# 2019_Dashboard_2_4_19.net
KiCad netlist of a schematic drawn in EAGLE
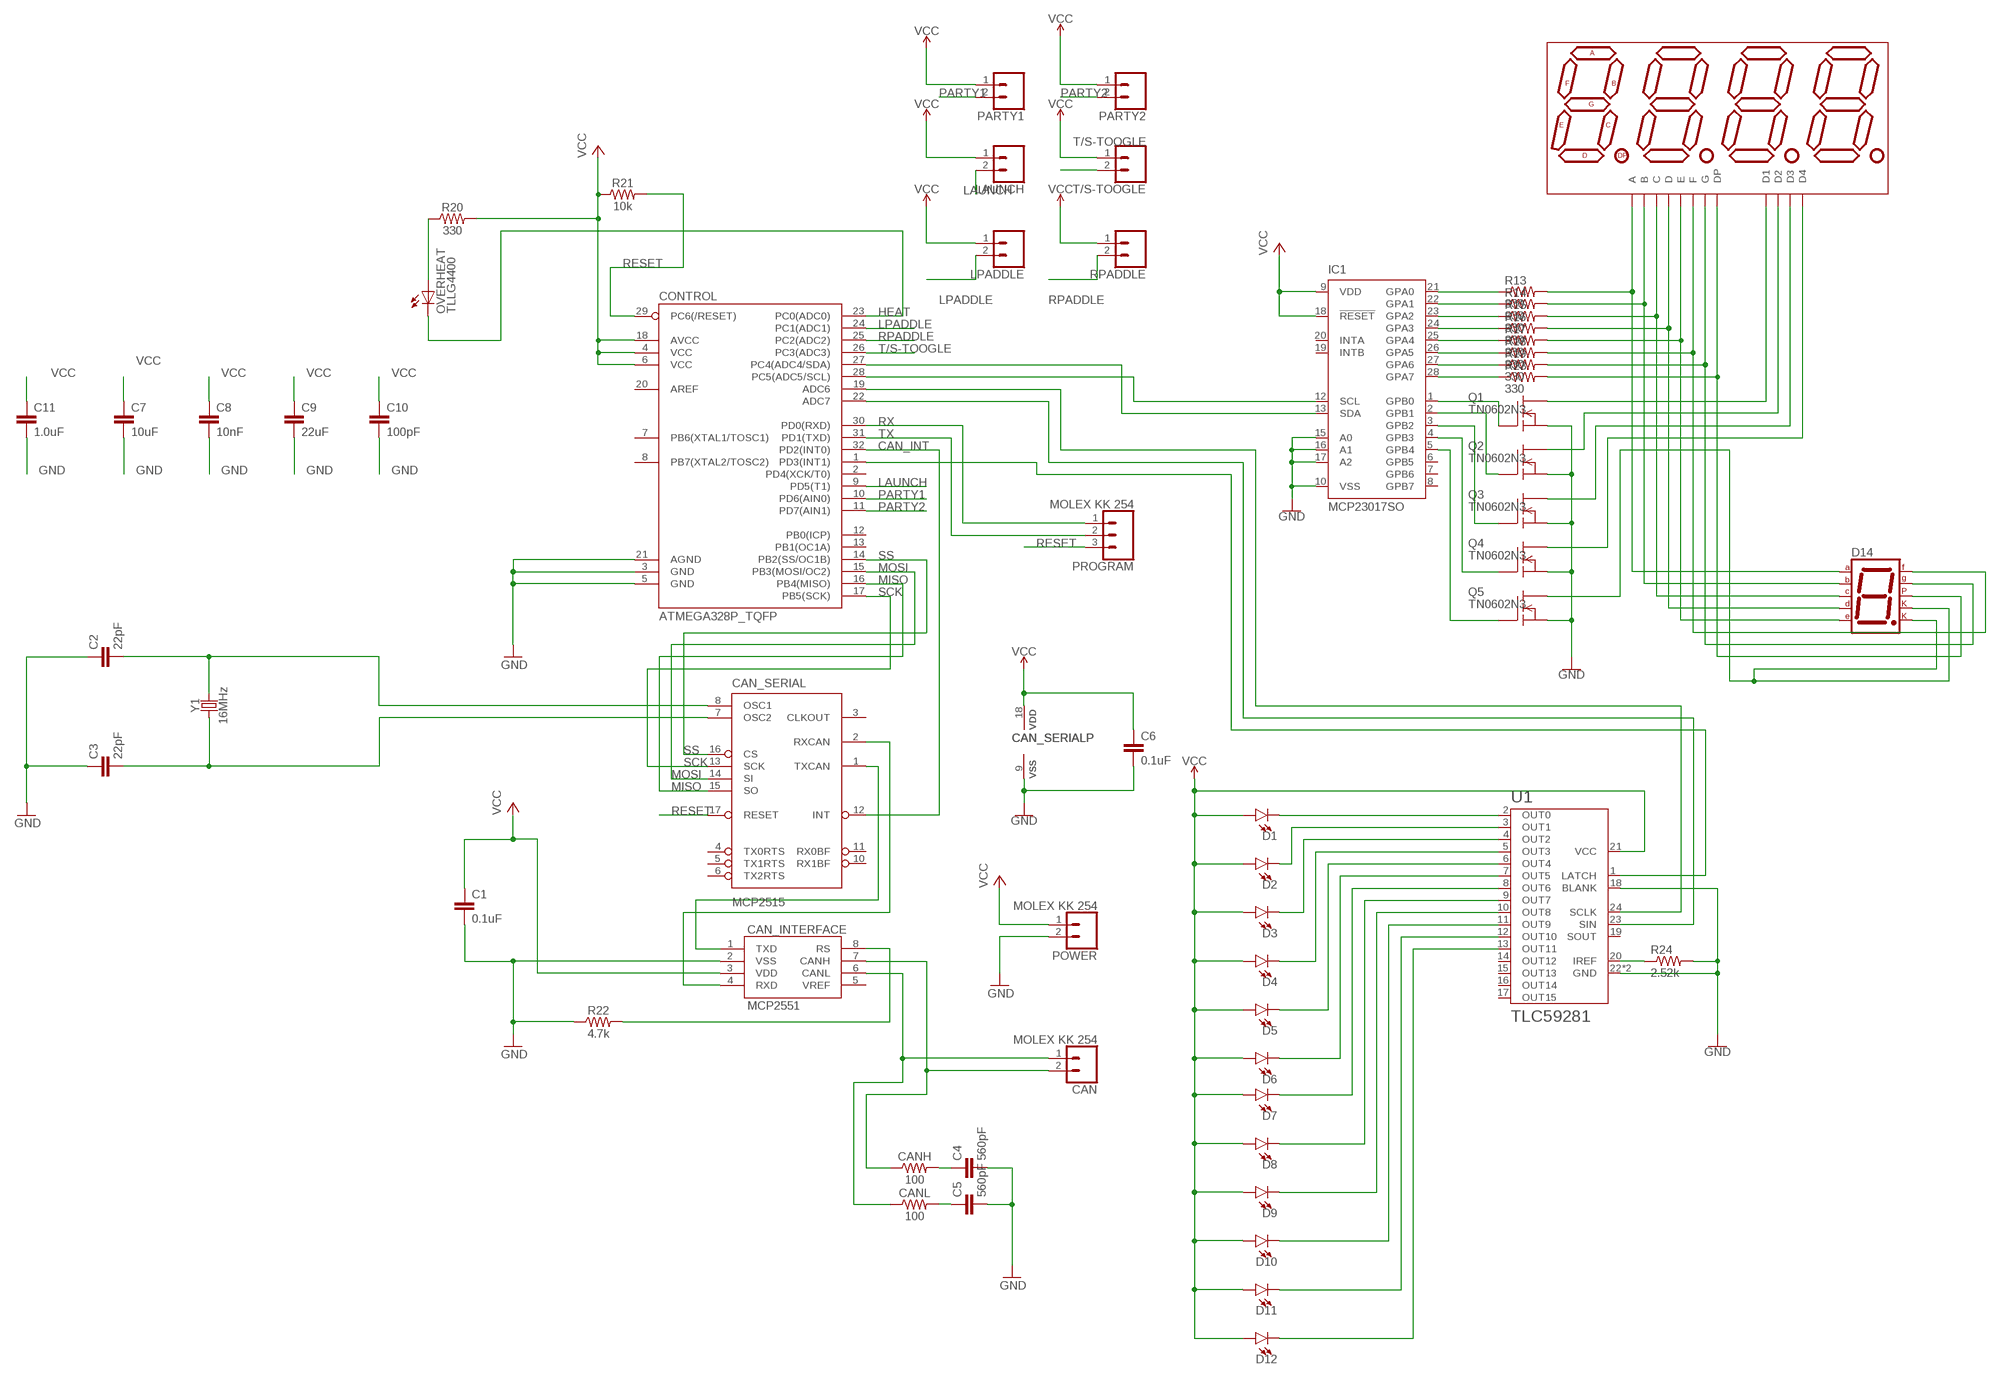
[diagram p0: schematic, sheet 1]

(export (version "E")
  (design (tool "Eeschema 10.0.6"))
  (components
    (comp (ref "C1")
      (value "0.1uF")
      (footprint "eagle-import:0603")
      (libsource (lib "eagle-import") (part "0.1UF-0603-25V-(+80/-20%)"))
    )
    (comp (ref "C2")
      (value "22pF")
      (footprint "eagle-import:0603")
      (libsource (lib "eagle-import") (part "22PF-0603-50V-5%"))
    )
    (comp (ref "C3")
      (value "22pF")
      (footprint "eagle-import:0603")
      (libsource (lib "eagle-import") (part "22PF-0603-50V-5%"))
    )
    (comp (ref "C4")
      (value "560pF")
      (footprint "eagle-import:0603")
      (libsource (lib "eagle-import") (part "560PF-0603-50V-5%"))
    )
    (comp (ref "C5")
      (value "560pF")
      (footprint "eagle-import:0603")
      (libsource (lib "eagle-import") (part "560PF-0603-50V-5%"))
    )
    (comp (ref "C6")
      (value "0.1uF")
      (footprint "eagle-import:0402")
      (libsource (lib "eagle-import") (part "0.1UF-0402-16V-10%"))
    )
    (comp (ref "C7")
      (value "10uF")
      (footprint "eagle-import:0805")
      (libsource (lib "eagle-import") (part "10UF-0805-10V-10%"))
    )
    (comp (ref "C8")
      (value "10nF")
      (footprint "eagle-import:0603")
      (libsource (lib "eagle-import") (part "10NF-0603-50V-10%"))
    )
    (comp (ref "C9")
      (value "22uF")
      (footprint "eagle-import:0805")
      (libsource (lib "eagle-import") (part "22UF-0805-6.3V-20%"))
    )
    (comp (ref "C10")
      (value "100pF")
      (footprint "eagle-import:0603")
      (libsource (lib "eagle-import") (part "100PF-0603-50V-5%"))
    )
    (comp (ref "C11")
      (value "1.0uF")
      (footprint "eagle-import:0805")
      (libsource (lib "eagle-import") (part "1.0UF-0805-25V-(+80/-20%)"))
    )
    (comp (ref "CAN")
      (value "MOLEX KK 254")
      (footprint "eagle-import:1X02")
      (libsource (lib "eagle-import") (part "CONN_02"))
    )
    (comp (ref "CANH")
      (value "100")
      (footprint "eagle-import:0603")
      (libsource (lib "eagle-import") (part "100OHM-0603-1/4W-5%"))
    )
    (comp (ref "CANL")
      (value "100")
      (footprint "eagle-import:0603")
      (libsource (lib "eagle-import") (part "100OHM-0603-1/4W-5%"))
    )
    (comp (ref "CAN_INTERFACE")
      (value "MCP2551")
      (footprint "eagle-import:SO08")
      (libsource (lib "eagle-import") (part "MCP2551"))
    )
    (comp (ref "CAN_SERIAL")
      (value "MCP2515")
      (footprint "eagle-import:SO18W")
      (libsource (lib "eagle-import") (part "MCP2515(MCP2510)SO"))
    )
    (comp (ref "CONTROL")
      (value "ATMEGA328P_TQFP")
      (footprint "eagle-import:TQFP32-08")
      (libsource (lib "eagle-import") (part "ATMEGA328P_TQFP"))
    )
    (comp (ref "D1")
      (value "LED5MM")
      (footprint "eagle-import:LED_5MM")
      (libsource (lib "eagle-import") (part "LED5MM"))
    )
    (comp (ref "D2")
      (value "LED5MM")
      (footprint "eagle-import:LED_5MM")
      (libsource (lib "eagle-import") (part "LED5MM"))
    )
    (comp (ref "D3")
      (value "LED5MM")
      (footprint "eagle-import:LED_5MM")
      (libsource (lib "eagle-import") (part "LED5MM"))
    )
    (comp (ref "D4")
      (value "LED5MM")
      (footprint "eagle-import:LED_5MM")
      (libsource (lib "eagle-import") (part "LED5MM"))
    )
    (comp (ref "D5")
      (value "LED5MM")
      (footprint "eagle-import:LED_5MM")
      (libsource (lib "eagle-import") (part "LED5MM"))
    )
    (comp (ref "D6")
      (value "LED5MM")
      (footprint "eagle-import:LED_5MM")
      (libsource (lib "eagle-import") (part "LED5MM"))
    )
    (comp (ref "D7")
      (value "LED5MM")
      (footprint "eagle-import:LED_5MM")
      (libsource (lib "eagle-import") (part "LED5MM"))
    )
    (comp (ref "D8")
      (value "LED5MM")
      (footprint "eagle-import:LED_5MM")
      (libsource (lib "eagle-import") (part "LED5MM"))
    )
    (comp (ref "D9")
      (value "LED5MM")
      (footprint "eagle-import:LED_5MM")
      (libsource (lib "eagle-import") (part "LED5MM"))
    )
    (comp (ref "D10")
      (value "LED5MM")
      (footprint "eagle-import:LED_5MM")
      (libsource (lib "eagle-import") (part "LED5MM"))
    )
    (comp (ref "D11")
      (value "LED5MM")
      (footprint "eagle-import:LED_5MM")
      (libsource (lib "eagle-import") (part "LED5MM"))
    )
    (comp (ref "D12")
      (value "LED5MM")
      (footprint "eagle-import:LED_5MM")
      (libsource (lib "eagle-import") (part "LED5MM"))
    )
    (comp (ref "D14")
      (value "7SEG-CK")
      (footprint "eagle-import:7SEG-13")
      (libsource (lib "eagle-import") (part "7SEG-CK"))
    )
    (comp (ref "DISP1")
      (value "ATA8041ARBJ")
      (footprint "eagle-import:7-SEGMENT-4DIGIT-20MM")
      (libsource (lib "eagle-import") (part "7-SEGMENT-4DIGIT-20MM-RED"))
    )
    (comp (ref "IC1")
      (value "MCP23017SO")
      (footprint "eagle-import:SO28W")
      (libsource (lib "eagle-import") (part "MCP23017SO"))
    )
    (comp (ref "LAUNCH")
      (value "CONN_02LOCK")
      (footprint "eagle-import:1X02_LOCK")
      (libsource (lib "eagle-import") (part "CONN_02LOCK"))
    )
    (comp (ref "LPADDLE")
      (value "CONN_02LOCK")
      (footprint "eagle-import:1X02_LOCK")
      (libsource (lib "eagle-import") (part "CONN_02LOCK"))
    )
    (comp (ref "OVERHEAT")
      (value "TLLG4400")
      (footprint "eagle-import:LED3MM")
      (fields (field (name "MF") "VISHAY SEMICONDUCTOR"))
      (libsource (lib "eagle-import") (part "TLLG4400"))
    )
    (comp (ref "PARTY1")
      (value "CONN_02LOCK")
      (footprint "eagle-import:1X02_LOCK")
      (libsource (lib "eagle-import") (part "CONN_02LOCK"))
    )
    (comp (ref "PARTY2")
      (value "CONN_02LOCK")
      (footprint "eagle-import:1X02_LOCK")
      (libsource (lib "eagle-import") (part "CONN_02LOCK"))
    )
    (comp (ref "POWER")
      (value "MOLEX KK 254")
      (footprint "eagle-import:1X02")
      (libsource (lib "eagle-import") (part "CONN_02"))
    )
    (comp (ref "PROGRAM")
      (value "MOLEX KK 254")
      (footprint "eagle-import:1X03")
      (libsource (lib "eagle-import") (part "CONN_03"))
    )
    (comp (ref "Q1")
      (value "TN0602N3")
      (footprint "eagle-import:TO-92")
      (libsource (lib "eagle-import") (part "TN0602N3"))
    )
    (comp (ref "Q2")
      (value "TN0602N3")
      (footprint "eagle-import:TO-92")
      (libsource (lib "eagle-import") (part "TN0602N3"))
    )
    (comp (ref "Q3")
      (value "TN0602N3")
      (footprint "eagle-import:TO-92")
      (libsource (lib "eagle-import") (part "TN0602N3"))
    )
    (comp (ref "Q4")
      (value "TN0602N3")
      (footprint "eagle-import:TO-92")
      (libsource (lib "eagle-import") (part "TN0602N3"))
    )
    (comp (ref "Q5")
      (value "TN0602N3")
      (footprint "eagle-import:TO-92")
      (libsource (lib "eagle-import") (part "TN0602N3"))
    )
    (comp (ref "R13")
      (value "330")
      (footprint "eagle-import:R0603")
      (libsource (lib "eagle-import") (part "R-US_R0603"))
    )
    (comp (ref "R14")
      (value "330")
      (footprint "eagle-import:R0603")
      (libsource (lib "eagle-import") (part "R-US_R0603"))
    )
    (comp (ref "R15")
      (value "330")
      (footprint "eagle-import:R0603")
      (libsource (lib "eagle-import") (part "R-US_R0603"))
    )
    (comp (ref "R16")
      (value "330")
      (footprint "eagle-import:R0603")
      (libsource (lib "eagle-import") (part "R-US_R0603"))
    )
    (comp (ref "R17")
      (value "330")
      (footprint "eagle-import:R0603")
      (libsource (lib "eagle-import") (part "R-US_R0603"))
    )
    (comp (ref "R18")
      (value "330")
      (footprint "eagle-import:R0603")
      (libsource (lib "eagle-import") (part "R-US_R0603"))
    )
    (comp (ref "R19")
      (value "330")
      (footprint "eagle-import:R0603")
      (libsource (lib "eagle-import") (part "R-US_R0603"))
    )
    (comp (ref "R20")
      (value "330")
      (footprint "eagle-import:0603")
      (libsource (lib "eagle-import") (part "330OHM-0603-1/10W-1%"))
    )
    (comp (ref "R21")
      (value "10k")
      (footprint "eagle-import:0603")
      (libsource (lib "eagle-import") (part "10KOHM-0603-1/10W-1%"))
    )
    (comp (ref "R22")
      (value "4.7k")
      (footprint "eagle-import:0603")
      (libsource (lib "eagle-import") (part "4.7KOHM-0603-1/10W-1%"))
    )
    (comp (ref "R23")
      (value "330")
      (footprint "eagle-import:R0603")
      (libsource (lib "eagle-import") (part "R-US_R0603"))
    )
    (comp (ref "R24")
      (value "2.52k")
      (footprint "eagle-import:R0603")
      (libsource (lib "eagle-import") (part "R-US_R0603"))
    )
    (comp (ref "RPADDLE")
      (value "CONN_02LOCK")
      (footprint "eagle-import:1X02_LOCK")
      (libsource (lib "eagle-import") (part "CONN_02LOCK"))
    )
    (comp (ref "T/S-TOOGLE")
      (value "CONN_02LOCK")
      (footprint "eagle-import:1X02_LOCK")
      (libsource (lib "eagle-import") (part "CONN_02LOCK"))
    )
    (comp (ref "U1")
      (value "TLC59281")
      (footprint "eagle-import:QFN-24")
      (fields (field (name "MF") "Texas Instruments"))
      (libsource (lib "eagle-import") (part "TLC59281"))
    )
    (comp (ref "Y1")
      (value "16MHz")
      (footprint "eagle-import:HC49US")
      (libsource (lib "eagle-import") (part "CRYSTAL-16MHZPTH-HC49US"))
    )
  )
  (nets
    (net (code "1") (name "/CAN_INT") (class "Default")
      (node (ref "CAN_SERIAL") (pin "12") (pinfunction "INT_12") (pintype "output"))
      (node (ref "CONTROL") (pin "32") (pinfunction "PD2(INT0)_32") (pintype "bidirectional"))
    )
    (net (code "2") (name "/HEAT") (class "Default")
      (node (ref "CONTROL") (pin "23") (pinfunction "PC0(ADC0)_23") (pintype "bidirectional"))
      (node (ref "OVERHEAT") (pin "K") (pinfunction "C_K") (pintype "passive"))
    )
    (net (code "3") (name "/LAUNCH") (class "Default")
      (node (ref "CONTROL") (pin "9") (pinfunction "PD5(T1)_9") (pintype "bidirectional"))
      (node (ref "LAUNCH") (pin "2") (pinfunction "2_2") (pintype "passive"))
    )
    (net (code "4") (name "/LPADDLE") (class "Default")
      (node (ref "CONTROL") (pin "24") (pinfunction "PC1(ADC1)_24") (pintype "bidirectional"))
      (node (ref "LPADDLE") (pin "2") (pinfunction "2_2") (pintype "passive"))
    )
    (net (code "5") (name "/MISO") (class "Default")
      (node (ref "CAN_SERIAL") (pin "15") (pinfunction "SO_15") (pintype "output"))
      (node (ref "CONTROL") (pin "16") (pinfunction "PB4(MISO)_16") (pintype "bidirectional"))
    )
    (net (code "6") (name "/MOSI") (class "Default")
      (node (ref "CAN_SERIAL") (pin "14") (pinfunction "SI_14") (pintype "input"))
      (node (ref "CONTROL") (pin "15") (pinfunction "PB3(MOSI/OC2)_15") (pintype "bidirectional"))
    )
    (net (code "7") (name "/PARTY1") (class "Default")
      (node (ref "CONTROL") (pin "10") (pinfunction "PD6(AIN0)_10") (pintype "bidirectional"))
      (node (ref "PARTY1") (pin "2") (pinfunction "2_2") (pintype "passive"))
    )
    (net (code "8") (name "/PARTY2") (class "Default")
      (node (ref "CONTROL") (pin "11") (pinfunction "PD7(AIN1)_11") (pintype "bidirectional"))
      (node (ref "PARTY2") (pin "2") (pinfunction "2_2") (pintype "passive"))
    )
    (net (code "9") (name "/RESET") (class "Default")
      (node (ref "CAN_SERIAL") (pin "17") (pinfunction "RESET_17") (pintype "input"))
      (node (ref "CONTROL") (pin "29") (pinfunction "PC6(/RESET)_29") (pintype "bidirectional"))
      (node (ref "PROGRAM") (pin "3") (pinfunction "3_3") (pintype "passive"))
      (node (ref "R21") (pin "2") (pinfunction "2_2") (pintype "passive"))
    )
    (net (code "10") (name "/RPADDLE") (class "Default")
      (node (ref "CONTROL") (pin "25") (pinfunction "PC2(ADC2)_25") (pintype "bidirectional"))
      (node (ref "RPADDLE") (pin "2") (pinfunction "2_2") (pintype "passive"))
    )
    (net (code "11") (name "/RX") (class "Default")
      (node (ref "CONTROL") (pin "30") (pinfunction "PD0(RXD)_30") (pintype "bidirectional"))
      (node (ref "PROGRAM") (pin "1") (pinfunction "1_1") (pintype "passive"))
    )
    (net (code "12") (name "/SCK") (class "Default")
      (node (ref "CAN_SERIAL") (pin "13") (pinfunction "SCK_13") (pintype "input"))
      (node (ref "CONTROL") (pin "17") (pinfunction "PB5(SCK)_17") (pintype "bidirectional"))
    )
    (net (code "13") (name "/SS") (class "Default")
      (node (ref "CAN_SERIAL") (pin "16") (pinfunction "CS_16") (pintype "input"))
      (node (ref "CONTROL") (pin "14") (pinfunction "PB2(SS/OC1B)_14") (pintype "bidirectional"))
    )
    (net (code "14") (name "/TX") (class "Default")
      (node (ref "CONTROL") (pin "31") (pinfunction "PD1(TXD)_31") (pintype "bidirectional"))
      (node (ref "PROGRAM") (pin "2") (pinfunction "2_2") (pintype "passive"))
    )
    (net (code "15") (name "/T{slash}S-TOOGLE") (class "Default")
      (node (ref "CONTROL") (pin "26") (pinfunction "PC3(ADC3)_26") (pintype "bidirectional"))
      (node (ref "T/S-TOOGLE") (pin "2") (pinfunction "2_2") (pintype "passive"))
    )
    (net (code "16") (name "GND") (class "Default")
      (node (ref "C1") (pin "2") (pinfunction "2_2") (pintype "passive"))
      (node (ref "C10") (pin "2") (pinfunction "2_2") (pintype "passive"))
      (node (ref "C11") (pin "2") (pinfunction "2_2") (pintype "passive"))
      (node (ref "C2") (pin "1") (pinfunction "1_1") (pintype "passive"))
      (node (ref "C3") (pin "1") (pinfunction "1_1") (pintype "passive"))
      (node (ref "C4") (pin "2") (pinfunction "2_2") (pintype "passive"))
      (node (ref "C5") (pin "2") (pinfunction "2_2") (pintype "passive"))
      (node (ref "C6") (pin "2") (pinfunction "2_2") (pintype "passive"))
      (node (ref "C7") (pin "2") (pinfunction "2_2") (pintype "passive"))
      (node (ref "C8") (pin "2") (pinfunction "2_2") (pintype "passive"))
      (node (ref "C9") (pin "2") (pinfunction "2_2") (pintype "passive"))
      (node (ref "CAN_INTERFACE") (pin "2") (pinfunction "VSS_2") (pintype "bidirectional"))
      (node (ref "CAN_SERIAL") (pin "9") (pinfunction "VSS_9") (pintype "power_in"))
      (node (ref "CONTROL") (pin "21") (pinfunction "AGND_21") (pintype "bidirectional"))
      (node (ref "CONTROL") (pin "3") (pinfunction "GND_3") (pintype "bidirectional"))
      (node (ref "CONTROL") (pin "5") (pinfunction "GND_5") (pintype "bidirectional"))
      (node (ref "IC1") (pin "10") (pinfunction "VSS_10") (pintype "power_in"))
      (node (ref "IC1") (pin "15") (pinfunction "A0_15") (pintype "input"))
      (node (ref "IC1") (pin "16") (pinfunction "A1_16") (pintype "input"))
      (node (ref "IC1") (pin "17") (pinfunction "A2_17") (pintype "input"))
      (node (ref "POWER") (pin "2") (pinfunction "2_2") (pintype "passive"))
      (node (ref "Q1") (pin "1") (pinfunction "S_1") (pintype "passive"))
      (node (ref "Q2") (pin "1") (pinfunction "S_1") (pintype "passive"))
      (node (ref "Q3") (pin "1") (pinfunction "S_1") (pintype "passive"))
      (node (ref "Q4") (pin "1") (pinfunction "S_1") (pintype "passive"))
      (node (ref "Q5") (pin "1") (pinfunction "S_1") (pintype "passive"))
      (node (ref "R22") (pin "1") (pinfunction "1_1") (pintype "passive"))
      (node (ref "R24") (pin "2") (pinfunction "2_2") (pintype "passive"))
      (node (ref "U1") (pin "18") (pinfunction "BLANK_18") (pintype "bidirectional"))
      (node (ref "U1") (pin "22") (pinfunction "GND_22") (pintype "bidirectional"))
      (node (ref "U1") (pin "EP") (pinfunction "GND_EP") (pintype "bidirectional"))
    )
    (net (code "17") (name "Net-(C4-Pad1)") (class "Default")
      (node (ref "C4") (pin "1") (pinfunction "1_1") (pintype "passive"))
      (node (ref "CANH") (pin "2") (pinfunction "2_2") (pintype "passive"))
    )
    (net (code "18") (name "Net-(C5-Pad1)") (class "Default")
      (node (ref "C5") (pin "1") (pinfunction "1_1") (pintype "passive"))
      (node (ref "CANL") (pin "2") (pinfunction "2_2") (pintype "passive"))
    )
    (net (code "19") (name "Net-(CAN_INTERFACE-CANH)") (class "Default")
      (node (ref "CAN") (pin "2") (pinfunction "2_2") (pintype "passive"))
      (node (ref "CANH") (pin "1") (pinfunction "1_1") (pintype "passive"))
      (node (ref "CAN_INTERFACE") (pin "7") (pinfunction "CANH_7") (pintype "bidirectional"))
    )
    (net (code "20") (name "Net-(CAN_INTERFACE-CANL)") (class "Default")
      (node (ref "CAN") (pin "1") (pinfunction "1_1") (pintype "passive"))
      (node (ref "CANL") (pin "1") (pinfunction "1_1") (pintype "passive"))
      (node (ref "CAN_INTERFACE") (pin "6") (pinfunction "CANL_6") (pintype "bidirectional"))
    )
    (net (code "21") (name "Net-(CAN_INTERFACE-RS)") (class "Default")
      (node (ref "CAN_INTERFACE") (pin "8") (pinfunction "RS_8") (pintype "bidirectional"))
      (node (ref "R22") (pin "2") (pinfunction "2_2") (pintype "passive"))
    )
    (net (code "22") (name "Net-(CAN_INTERFACE-RXD)") (class "Default")
      (node (ref "CAN_INTERFACE") (pin "4") (pinfunction "RXD_4") (pintype "bidirectional"))
      (node (ref "CAN_SERIAL") (pin "2") (pinfunction "RXCAN_2") (pintype "input"))
    )
    (net (code "23") (name "Net-(CAN_INTERFACE-TXD)") (class "Default")
      (node (ref "CAN_INTERFACE") (pin "1") (pinfunction "TXD_1") (pintype "bidirectional"))
      (node (ref "CAN_SERIAL") (pin "1") (pinfunction "TXCAN_1") (pintype "output"))
    )
    (net (code "24") (name "Net-(CAN_SERIALA-OSC1)") (class "Default")
      (node (ref "C2") (pin "2") (pinfunction "2_2") (pintype "passive"))
      (node (ref "CAN_SERIAL") (pin "8") (pinfunction "OSC1_8") (pintype "input"))
      (node (ref "Y1") (pin "2") (pinfunction "2_2") (pintype "passive"))
    )
    (net (code "25") (name "Net-(CAN_SERIALA-OSC2)") (class "Default")
      (node (ref "C3") (pin "2") (pinfunction "2_2") (pintype "passive"))
      (node (ref "CAN_SERIAL") (pin "7") (pinfunction "OSC2_7") (pintype "output"))
      (node (ref "Y1") (pin "1") (pinfunction "1_1") (pintype "passive"))
    )
    (net (code "26") (name "Net-(CONTROL-ADC6)") (class "Default")
      (node (ref "CONTROL") (pin "19") (pinfunction "ADC6_19") (pintype "bidirectional"))
      (node (ref "U1") (pin "24") (pinfunction "SCLK_24") (pintype "bidirectional"))
    )
    (net (code "27") (name "Net-(CONTROL-ADC7)") (class "Default")
      (node (ref "CONTROL") (pin "22") (pinfunction "ADC7_22") (pintype "bidirectional"))
      (node (ref "U1") (pin "23") (pinfunction "SIN_23") (pintype "bidirectional"))
    )
    (net (code "28") (name "Net-(CONTROL-PC4(ADC4{slash}SDA))") (class "Default")
      (node (ref "CONTROL") (pin "27") (pinfunction "PC4(ADC4/SDA)_27") (pintype "bidirectional"))
      (node (ref "IC1") (pin "13") (pinfunction "SDA_13") (pintype "bidirectional"))
    )
    (net (code "29") (name "Net-(CONTROL-PC5(ADC5{slash}SCL))") (class "Default")
      (node (ref "CONTROL") (pin "28") (pinfunction "PC5(ADC5/SCL)_28") (pintype "bidirectional"))
      (node (ref "IC1") (pin "12") (pinfunction "SCL_12") (pintype "input"))
    )
    (net (code "30") (name "Net-(CONTROL-PD3(INT1))") (class "Default")
      (node (ref "CONTROL") (pin "1") (pinfunction "PD3(INT1)_1") (pintype "bidirectional"))
      (node (ref "U1") (pin "1") (pinfunction "LATCH_1") (pintype "bidirectional"))
    )
    (net (code "31") (name "Net-(D1-C)") (class "Default")
      (node (ref "D1") (pin "K") (pinfunction "C_K") (pintype "passive"))
      (node (ref "U1") (pin "2") (pinfunction "OUT0_2") (pintype "bidirectional"))
    )
    (net (code "32") (name "Net-(D2-C)") (class "Default")
      (node (ref "D2") (pin "K") (pinfunction "C_K") (pintype "passive"))
      (node (ref "U1") (pin "3") (pinfunction "OUT1_3") (pintype "bidirectional"))
    )
    (net (code "33") (name "Net-(D3-C)") (class "Default")
      (node (ref "D3") (pin "K") (pinfunction "C_K") (pintype "passive"))
      (node (ref "U1") (pin "4") (pinfunction "OUT2_4") (pintype "bidirectional"))
    )
    (net (code "34") (name "Net-(D4-C)") (class "Default")
      (node (ref "D4") (pin "K") (pinfunction "C_K") (pintype "passive"))
      (node (ref "U1") (pin "5") (pinfunction "OUT3_5") (pintype "bidirectional"))
    )
    (net (code "35") (name "Net-(D5-C)") (class "Default")
      (node (ref "D5") (pin "K") (pinfunction "C_K") (pintype "passive"))
      (node (ref "U1") (pin "6") (pinfunction "OUT4_6") (pintype "bidirectional"))
    )
    (net (code "36") (name "Net-(D6-C)") (class "Default")
      (node (ref "D6") (pin "K") (pinfunction "C_K") (pintype "passive"))
      (node (ref "U1") (pin "7") (pinfunction "OUT5_7") (pintype "bidirectional"))
    )
    (net (code "37") (name "Net-(D7-C)") (class "Default")
      (node (ref "D7") (pin "K") (pinfunction "C_K") (pintype "passive"))
      (node (ref "U1") (pin "8") (pinfunction "OUT6_8") (pintype "bidirectional"))
    )
    (net (code "38") (name "Net-(D8-C)") (class "Default")
      (node (ref "D8") (pin "K") (pinfunction "C_K") (pintype "passive"))
      (node (ref "U1") (pin "9") (pinfunction "OUT7_9") (pintype "bidirectional"))
    )
    (net (code "39") (name "Net-(D9-C)") (class "Default")
      (node (ref "D9") (pin "K") (pinfunction "C_K") (pintype "passive"))
      (node (ref "U1") (pin "10") (pinfunction "OUT8_10") (pintype "bidirectional"))
    )
    (net (code "40") (name "Net-(D10-C)") (class "Default")
      (node (ref "D10") (pin "K") (pinfunction "C_K") (pintype "passive"))
      (node (ref "U1") (pin "11") (pinfunction "OUT9_11") (pintype "bidirectional"))
    )
    (net (code "41") (name "Net-(D11-C)") (class "Default")
      (node (ref "D11") (pin "K") (pinfunction "C_K") (pintype "passive"))
      (node (ref "U1") (pin "12") (pinfunction "OUT10_12") (pintype "bidirectional"))
    )
    (net (code "42") (name "Net-(D12-C)") (class "Default")
      (node (ref "D12") (pin "K") (pinfunction "C_K") (pintype "passive"))
      (node (ref "U1") (pin "13") (pinfunction "OUT11_13") (pintype "bidirectional"))
    )
    (net (code "43") (name "Net-(D14-A)") (class "Default")
      (node (ref "D14") (pin "7") (pinfunction "A_7") (pintype "passive"))
      (node (ref "DISP1") (pin "11") (pinfunction "A_11") (pintype "bidirectional"))
      (node (ref "R13") (pin "2") (pinfunction "2_2") (pintype "passive"))
    )
    (net (code "44") (name "Net-(D14-B)") (class "Default")
      (node (ref "D14") (pin "6") (pinfunction "B_6") (pintype "passive"))
      (node (ref "DISP1") (pin "7") (pinfunction "B_7") (pintype "bidirectional"))
      (node (ref "R14") (pin "2") (pinfunction "2_2") (pintype "passive"))
    )
    (net (code "45") (name "Net-(D14-C)") (class "Default")
      (node (ref "D14") (pin "4") (pinfunction "C_4") (pintype "passive"))
      (node (ref "DISP1") (pin "4") (pinfunction "C_4") (pintype "bidirectional"))
      (node (ref "R15") (pin "2") (pinfunction "2_2") (pintype "passive"))
    )
    (net (code "46") (name "Net-(D14-CK1)") (class "Default")
      (node (ref "D14") (pin "3") (pinfunction "CK1_3") (pintype "passive"))
      (node (ref "D14") (pin "8") (pinfunction "CK2_8") (pintype "passive"))
      (node (ref "Q5") (pin "3") (pinfunction "D_3") (pintype "passive"))
    )
    (net (code "47") (name "Net-(D14-D)") (class "Default")
      (node (ref "D14") (pin "2") (pinfunction "D_2") (pintype "passive"))
      (node (ref "DISP1") (pin "2") (pinfunction "D_2") (pintype "bidirectional"))
      (node (ref "R16") (pin "2") (pinfunction "2_2") (pintype "passive"))
    )
    (net (code "48") (name "Net-(D14-DP)") (class "Default")
      (node (ref "D14") (pin "5") (pinfunction "DP_5") (pintype "passive"))
      (node (ref "DISP1") (pin "3") (pinfunction "DP_3") (pintype "bidirectional"))
      (node (ref "R23") (pin "2") (pinfunction "2_2") (pintype "passive"))
    )
    (net (code "49") (name "Net-(D14-E)") (class "Default")
      (node (ref "D14") (pin "1") (pinfunction "E_1") (pintype "passive"))
      (node (ref "DISP1") (pin "1") (pinfunction "E_1") (pintype "bidirectional"))
      (node (ref "R17") (pin "2") (pinfunction "2_2") (pintype "passive"))
    )
    (net (code "50") (name "Net-(D14-F)") (class "Default")
      (node (ref "D14") (pin "9") (pinfunction "F_9") (pintype "passive"))
      (node (ref "DISP1") (pin "10") (pinfunction "F_10") (pintype "bidirectional"))
      (node (ref "R18") (pin "2") (pinfunction "2_2") (pintype "passive"))
    )
    (net (code "51") (name "Net-(D14-G)") (class "Default")
      (node (ref "D14") (pin "10") (pinfunction "G_10") (pintype "passive"))
      (node (ref "DISP1") (pin "5") (pinfunction "G_5") (pintype "bidirectional"))
      (node (ref "R19") (pin "2") (pinfunction "2_2") (pintype "passive"))
    )
    (net (code "52") (name "Net-(DISP1-D1)") (class "Default")
      (node (ref "DISP1") (pin "12") (pinfunction "D1_12") (pintype "bidirectional"))
      (node (ref "Q1") (pin "3") (pinfunction "D_3") (pintype "passive"))
    )
    (net (code "53") (name "Net-(DISP1-D2)") (class "Default")
      (node (ref "DISP1") (pin "9") (pinfunction "D2_9") (pintype "bidirectional"))
      (node (ref "Q2") (pin "3") (pinfunction "D_3") (pintype "passive"))
    )
    (net (code "54") (name "Net-(DISP1-D3)") (class "Default")
      (node (ref "DISP1") (pin "8") (pinfunction "D3_8") (pintype "bidirectional"))
      (node (ref "Q3") (pin "3") (pinfunction "D_3") (pintype "passive"))
    )
    (net (code "55") (name "Net-(DISP1-D4)") (class "Default")
      (node (ref "DISP1") (pin "6") (pinfunction "D4_6") (pintype "bidirectional"))
      (node (ref "Q4") (pin "3") (pinfunction "D_3") (pintype "passive"))
    )
    (net (code "56") (name "Net-(IC1-GPA0)") (class "Default")
      (node (ref "IC1") (pin "21") (pinfunction "GPA0_21") (pintype "bidirectional"))
      (node (ref "R13") (pin "1") (pinfunction "1_1") (pintype "passive"))
    )
    (net (code "57") (name "Net-(IC1-GPA1)") (class "Default")
      (node (ref "IC1") (pin "22") (pinfunction "GPA1_22") (pintype "bidirectional"))
      (node (ref "R14") (pin "1") (pinfunction "1_1") (pintype "passive"))
    )
    (net (code "58") (name "Net-(IC1-GPA2)") (class "Default")
      (node (ref "IC1") (pin "23") (pinfunction "GPA2_23") (pintype "bidirectional"))
      (node (ref "R15") (pin "1") (pinfunction "1_1") (pintype "passive"))
    )
    (net (code "59") (name "Net-(IC1-GPA3)") (class "Default")
      (node (ref "IC1") (pin "24") (pinfunction "GPA3_24") (pintype "bidirectional"))
      (node (ref "R16") (pin "1") (pinfunction "1_1") (pintype "passive"))
    )
    (net (code "60") (name "Net-(IC1-GPA4)") (class "Default")
      (node (ref "IC1") (pin "25") (pinfunction "GPA4_25") (pintype "bidirectional"))
      (node (ref "R17") (pin "1") (pinfunction "1_1") (pintype "passive"))
    )
    (net (code "61") (name "Net-(IC1-GPA5)") (class "Default")
      (node (ref "IC1") (pin "26") (pinfunction "GPA5_26") (pintype "bidirectional"))
      (node (ref "R18") (pin "1") (pinfunction "1_1") (pintype "passive"))
    )
    (net (code "62") (name "Net-(IC1-GPA6)") (class "Default")
      (node (ref "IC1") (pin "27") (pinfunction "GPA6_27") (pintype "bidirectional"))
      (node (ref "R19") (pin "1") (pinfunction "1_1") (pintype "passive"))
    )
    (net (code "63") (name "Net-(IC1-GPA7)") (class "Default")
      (node (ref "IC1") (pin "28") (pinfunction "GPA7_28") (pintype "bidirectional"))
      (node (ref "R23") (pin "1") (pinfunction "1_1") (pintype "passive"))
    )
    (net (code "64") (name "Net-(IC1-GPB0)") (class "Default")
      (node (ref "IC1") (pin "1") (pinfunction "GPB0_1") (pintype "bidirectional"))
      (node (ref "Q1") (pin "2") (pinfunction "G_2") (pintype "passive"))
    )
    (net (code "65") (name "Net-(IC1-GPB1)") (class "Default")
      (node (ref "IC1") (pin "2") (pinfunction "GPB1_2") (pintype "bidirectional"))
      (node (ref "Q2") (pin "2") (pinfunction "G_2") (pintype "passive"))
    )
    (net (code "66") (name "Net-(IC1-GPB2)") (class "Default")
      (node (ref "IC1") (pin "3") (pinfunction "GPB2_3") (pintype "bidirectional"))
      (node (ref "Q3") (pin "2") (pinfunction "G_2") (pintype "passive"))
    )
    (net (code "67") (name "Net-(IC1-GPB3)") (class "Default")
      (node (ref "IC1") (pin "4") (pinfunction "GPB3_4") (pintype "bidirectional"))
      (node (ref "Q4") (pin "2") (pinfunction "G_2") (pintype "passive"))
    )
    (net (code "68") (name "Net-(IC1-GPB4)") (class "Default")
      (node (ref "IC1") (pin "5") (pinfunction "GPB4_5") (pintype "bidirectional"))
      (node (ref "Q5") (pin "2") (pinfunction "G_2") (pintype "passive"))
    )
    (net (code "69") (name "Net-(OVERHEAT-PadA)") (class "Default")
      (node (ref "OVERHEAT") (pin "A") (pinfunction "A_A") (pintype "passive"))
      (node (ref "R20") (pin "1") (pinfunction "1_1") (pintype "passive"))
    )
    (net (code "70") (name "Net-(U1-IREF)") (class "Default")
      (node (ref "R24") (pin "1") (pinfunction "1_1") (pintype "passive"))
      (node (ref "U1") (pin "20") (pinfunction "IREF_20") (pintype "bidirectional"))
    )
    (net (code "71") (name "VCC") (class "Default")
      (node (ref "C1") (pin "1") (pinfunction "1_1") (pintype "passive"))
      (node (ref "C10") (pin "1") (pinfunction "1_1") (pintype "passive"))
      (node (ref "C11") (pin "1") (pinfunction "1_1") (pintype "passive"))
      (node (ref "C6") (pin "1") (pinfunction "1_1") (pintype "passive"))
      (node (ref "C7") (pin "1") (pinfunction "1_1") (pintype "passive"))
      (node (ref "C8") (pin "1") (pinfunction "1_1") (pintype "passive"))
      (node (ref "C9") (pin "1") (pinfunction "1_1") (pintype "passive"))
      (node (ref "CAN_INTERFACE") (pin "3") (pinfunction "VDD_3") (pintype "bidirectional"))
      (node (ref "CAN_SERIAL") (pin "18") (pinfunction "VDD_18") (pintype "power_in"))
      (node (ref "CONTROL") (pin "18") (pinfunction "AVCC_18") (pintype "bidirectional"))
      (node (ref "CONTROL") (pin "4") (pinfunction "VCC_4") (pintype "bidirectional"))
      (node (ref "CONTROL") (pin "6") (pinfunction "VCC_6") (pintype "bidirectional"))
      (node (ref "D1") (pin "A") (pinfunction "A_A") (pintype "passive"))
      (node (ref "D10") (pin "A") (pinfunction "A_A") (pintype "passive"))
      (node (ref "D11") (pin "A") (pinfunction "A_A") (pintype "passive"))
      (node (ref "D12") (pin "A") (pinfunction "A_A") (pintype "passive"))
      (node (ref "D2") (pin "A") (pinfunction "A_A") (pintype "passive"))
      (node (ref "D3") (pin "A") (pinfunction "A_A") (pintype "passive"))
      (node (ref "D4") (pin "A") (pinfunction "A_A") (pintype "passive"))
      (node (ref "D5") (pin "A") (pinfunction "A_A") (pintype "passive"))
      (node (ref "D6") (pin "A") (pinfunction "A_A") (pintype "passive"))
      (node (ref "D7") (pin "A") (pinfunction "A_A") (pintype "passive"))
      (node (ref "D8") (pin "A") (pinfunction "A_A") (pintype "passive"))
      (node (ref "D9") (pin "A") (pinfunction "A_A") (pintype "passive"))
      (node (ref "IC1") (pin "18") (pinfunction "~{RESET}_18") (pintype "input"))
      (node (ref "IC1") (pin "9") (pinfunction "VDD_9") (pintype "power_in"))
      (node (ref "LAUNCH") (pin "1") (pinfunction "1_1") (pintype "passive"))
      (node (ref "LPADDLE") (pin "1") (pinfunction "1_1") (pintype "passive"))
      (node (ref "PARTY1") (pin "1") (pinfunction "1_1") (pintype "passive"))
      (node (ref "PARTY2") (pin "1") (pinfunction "1_1") (pintype "passive"))
      (node (ref "POWER") (pin "1") (pinfunction "1_1") (pintype "passive"))
      (node (ref "R20") (pin "2") (pinfunction "2_2") (pintype "passive"))
      (node (ref "R21") (pin "1") (pinfunction "1_1") (pintype "passive"))
      (node (ref "RPADDLE") (pin "1") (pinfunction "1_1") (pintype "passive"))
      (node (ref "T/S-TOOGLE") (pin "1") (pinfunction "1_1") (pintype "passive"))
      (node (ref "U1") (pin "21") (pinfunction "VCC_21") (pintype "bidirectional"))
    )
    (net (code "72") (name "unconnected-(CAN_INTERFACE-VREF-Pad5)") (class "Default")
      (node (ref "CAN_INTERFACE") (pin "5") (pinfunction "VREF_5") (pintype "bidirectional"))
    )
    (net (code "73") (name "unconnected-(CAN_SERIALA-CLKOUT-Pad3)") (class "Default")
      (node (ref "CAN_SERIAL") (pin "3") (pinfunction "CLKOUT_3") (pintype "output"))
    )
    (net (code "74") (name "unconnected-(CAN_SERIALA-RX0BF-Pad11)") (class "Default")
      (node (ref "CAN_SERIAL") (pin "11") (pinfunction "RX0BF_11") (pintype "output"))
    )
    (net (code "75") (name "unconnected-(CAN_SERIALA-RX1BF-Pad10)") (class "Default")
      (node (ref "CAN_SERIAL") (pin "10") (pinfunction "RX1BF_10") (pintype "output"))
    )
    (net (code "76") (name "unconnected-(CAN_SERIALA-TX0RTS-Pad4)") (class "Default")
      (node (ref "CAN_SERIAL") (pin "4") (pinfunction "TX0RTS_4") (pintype "input"))
    )
    (net (code "77") (name "unconnected-(CAN_SERIALA-TX1RTS-Pad5)") (class "Default")
      (node (ref "CAN_SERIAL") (pin "5") (pinfunction "TX1RTS_5") (pintype "input"))
    )
    (net (code "78") (name "unconnected-(CAN_SERIALA-TX2RTS-Pad6)") (class "Default")
      (node (ref "CAN_SERIAL") (pin "6") (pinfunction "TX2RTS_6") (pintype "input"))
    )
    (net (code "79") (name "unconnected-(CONTROL-AREF-Pad20)") (class "Default")
      (node (ref "CONTROL") (pin "20") (pinfunction "AREF_20") (pintype "bidirectional"))
    )
    (net (code "80") (name "unconnected-(CONTROL-PB0(ICP)-Pad12)") (class "Default")
      (node (ref "CONTROL") (pin "12") (pinfunction "PB0(ICP)_12") (pintype "bidirectional"))
    )
    (net (code "81") (name "unconnected-(CONTROL-PB1(OC1A)-Pad13)") (class "Default")
      (node (ref "CONTROL") (pin "13") (pinfunction "PB1(OC1A)_13") (pintype "bidirectional"))
    )
    (net (code "82") (name "unconnected-(CONTROL-PB6(XTAL1{slash}TOSC1)-Pad7)") (class "Default")
      (node (ref "CONTROL") (pin "7") (pinfunction "PB6(XTAL1/TOSC1)_7") (pintype "bidirectional"))
    )
    (net (code "83") (name "unconnected-(CONTROL-PB7(XTAL2{slash}TOSC2)-Pad8)") (class "Default")
      (node (ref "CONTROL") (pin "8") (pinfunction "PB7(XTAL2/TOSC2)_8") (pintype "bidirectional"))
    )
    (net (code "84") (name "unconnected-(CONTROL-PD4(XCK{slash}T0)-Pad2)") (class "Default")
      (node (ref "CONTROL") (pin "2") (pinfunction "PD4(XCK/T0)_2") (pintype "bidirectional"))
    )
    (net (code "85") (name "unconnected-(IC1-GPB5-Pad6)") (class "Default")
      (node (ref "IC1") (pin "6") (pinfunction "GPB5_6") (pintype "bidirectional"))
    )
    (net (code "86") (name "unconnected-(IC1-GPB6-Pad7)") (class "Default")
      (node (ref "IC1") (pin "7") (pinfunction "GPB6_7") (pintype "bidirectional"))
    )
    (net (code "87") (name "unconnected-(IC1-GPB7-Pad8)") (class "Default")
      (node (ref "IC1") (pin "8") (pinfunction "GPB7_8") (pintype "bidirectional"))
    )
    (net (code "88") (name "unconnected-(IC1-INTA-Pad20)") (class "Default")
      (node (ref "IC1") (pin "20") (pinfunction "INTA_20") (pintype "output"))
    )
    (net (code "89") (name "unconnected-(IC1-INTB-Pad19)") (class "Default")
      (node (ref "IC1") (pin "19") (pinfunction "INTB_19") (pintype "output"))
    )
    (net (code "90") (name "unconnected-(U1-OUT12-Pad14)") (class "Default")
      (node (ref "U1") (pin "14") (pinfunction "OUT12_14") (pintype "bidirectional"))
    )
    (net (code "91") (name "unconnected-(U1-OUT13-Pad15)") (class "Default")
      (node (ref "U1") (pin "15") (pinfunction "OUT13_15") (pintype "bidirectional"))
    )
    (net (code "92") (name "unconnected-(U1-OUT14-Pad16)") (class "Default")
      (node (ref "U1") (pin "16") (pinfunction "OUT14_16") (pintype "bidirectional"))
    )
    (net (code "93") (name "unconnected-(U1-OUT15-Pad17)") (class "Default")
      (node (ref "U1") (pin "17") (pinfunction "OUT15_17") (pintype "bidirectional"))
    )
    (net (code "94") (name "unconnected-(U1-SOUT-Pad19)") (class "Default")
      (node (ref "U1") (pin "19") (pinfunction "SOUT_19") (pintype "bidirectional"))
    )
  )
)
